# mrShark_15.net
KiCad netlist of a schematic drawn in EAGLE
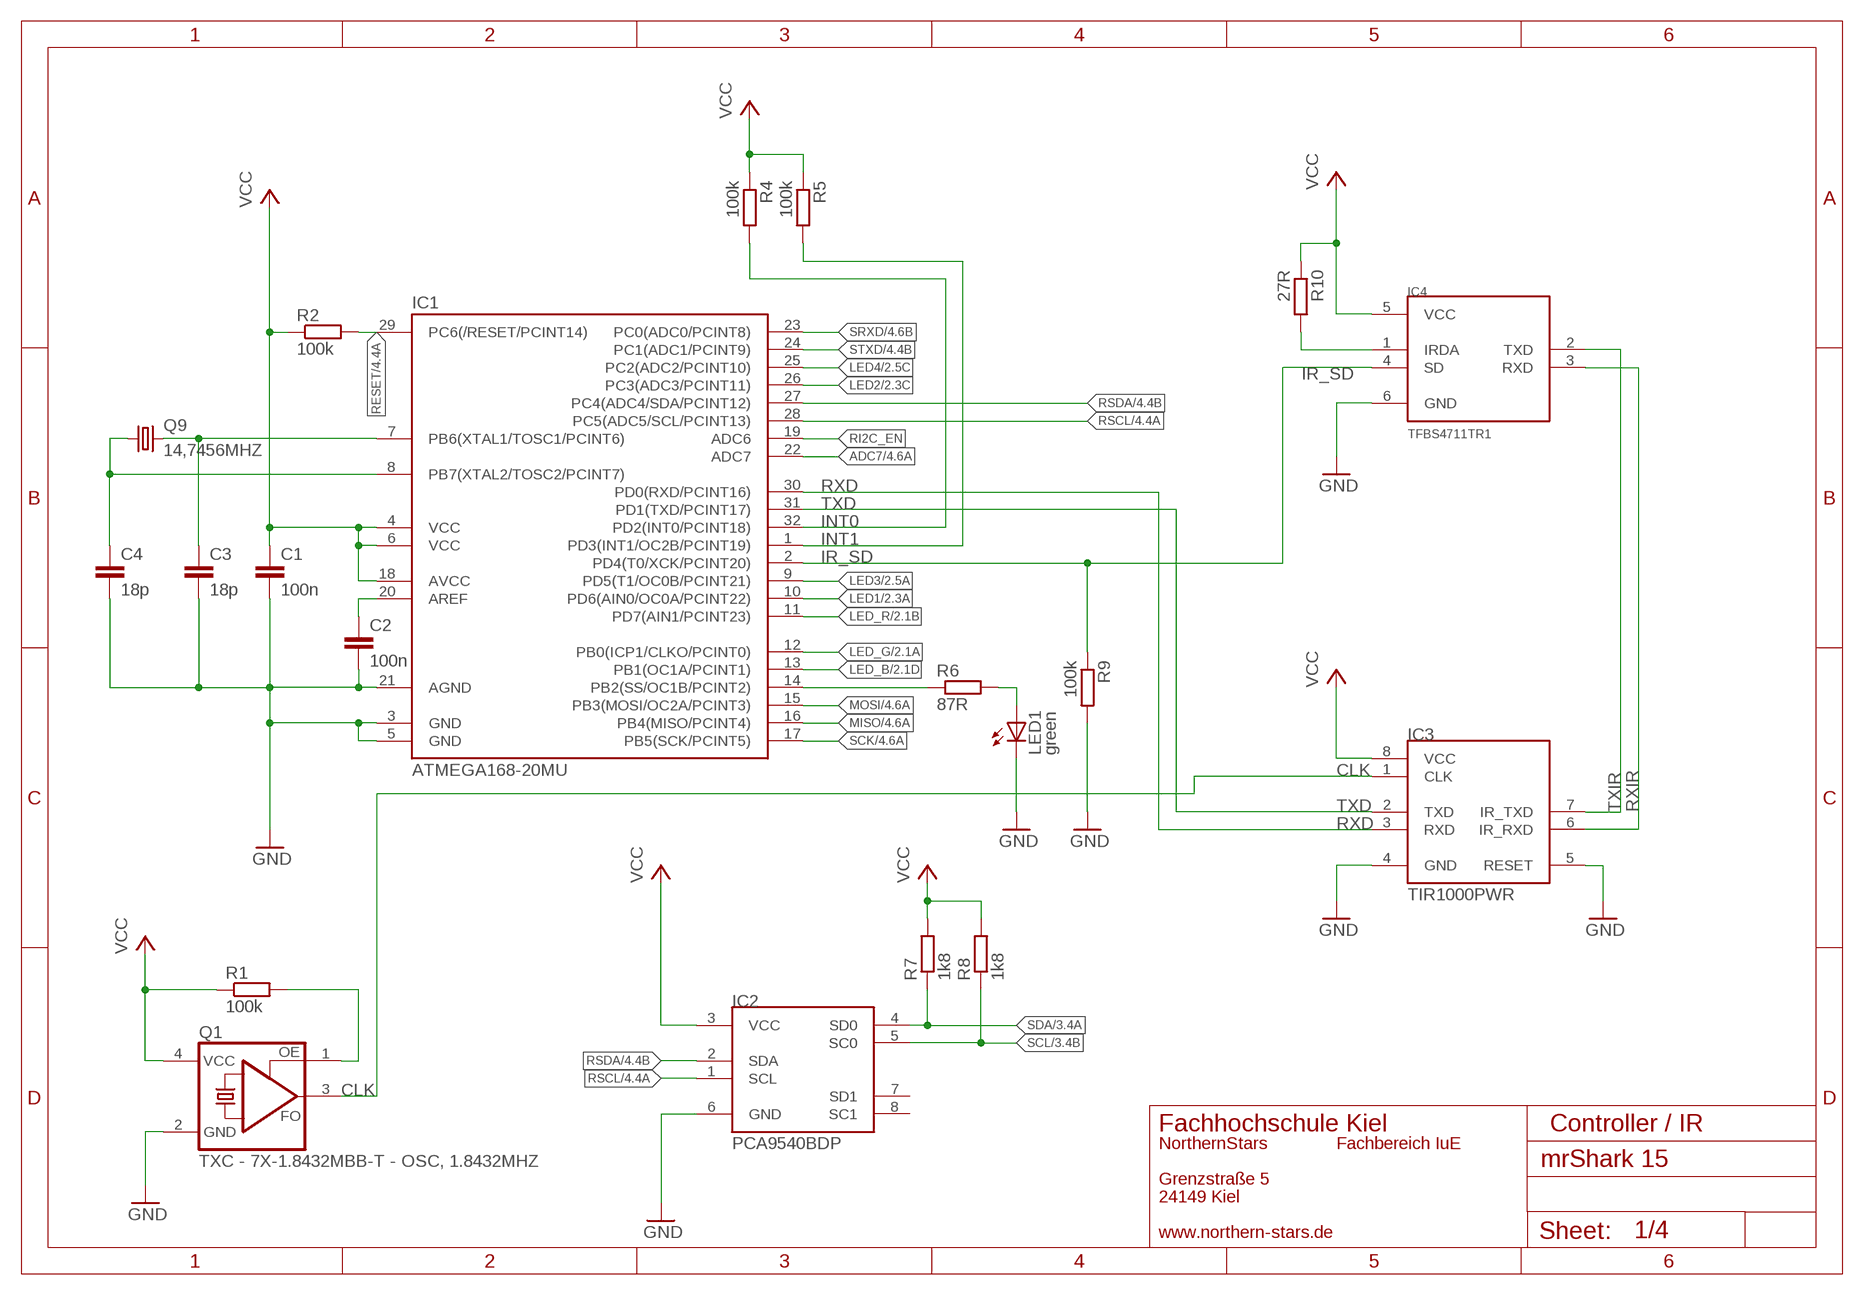
[diagram p0: schematic, sheet 1]
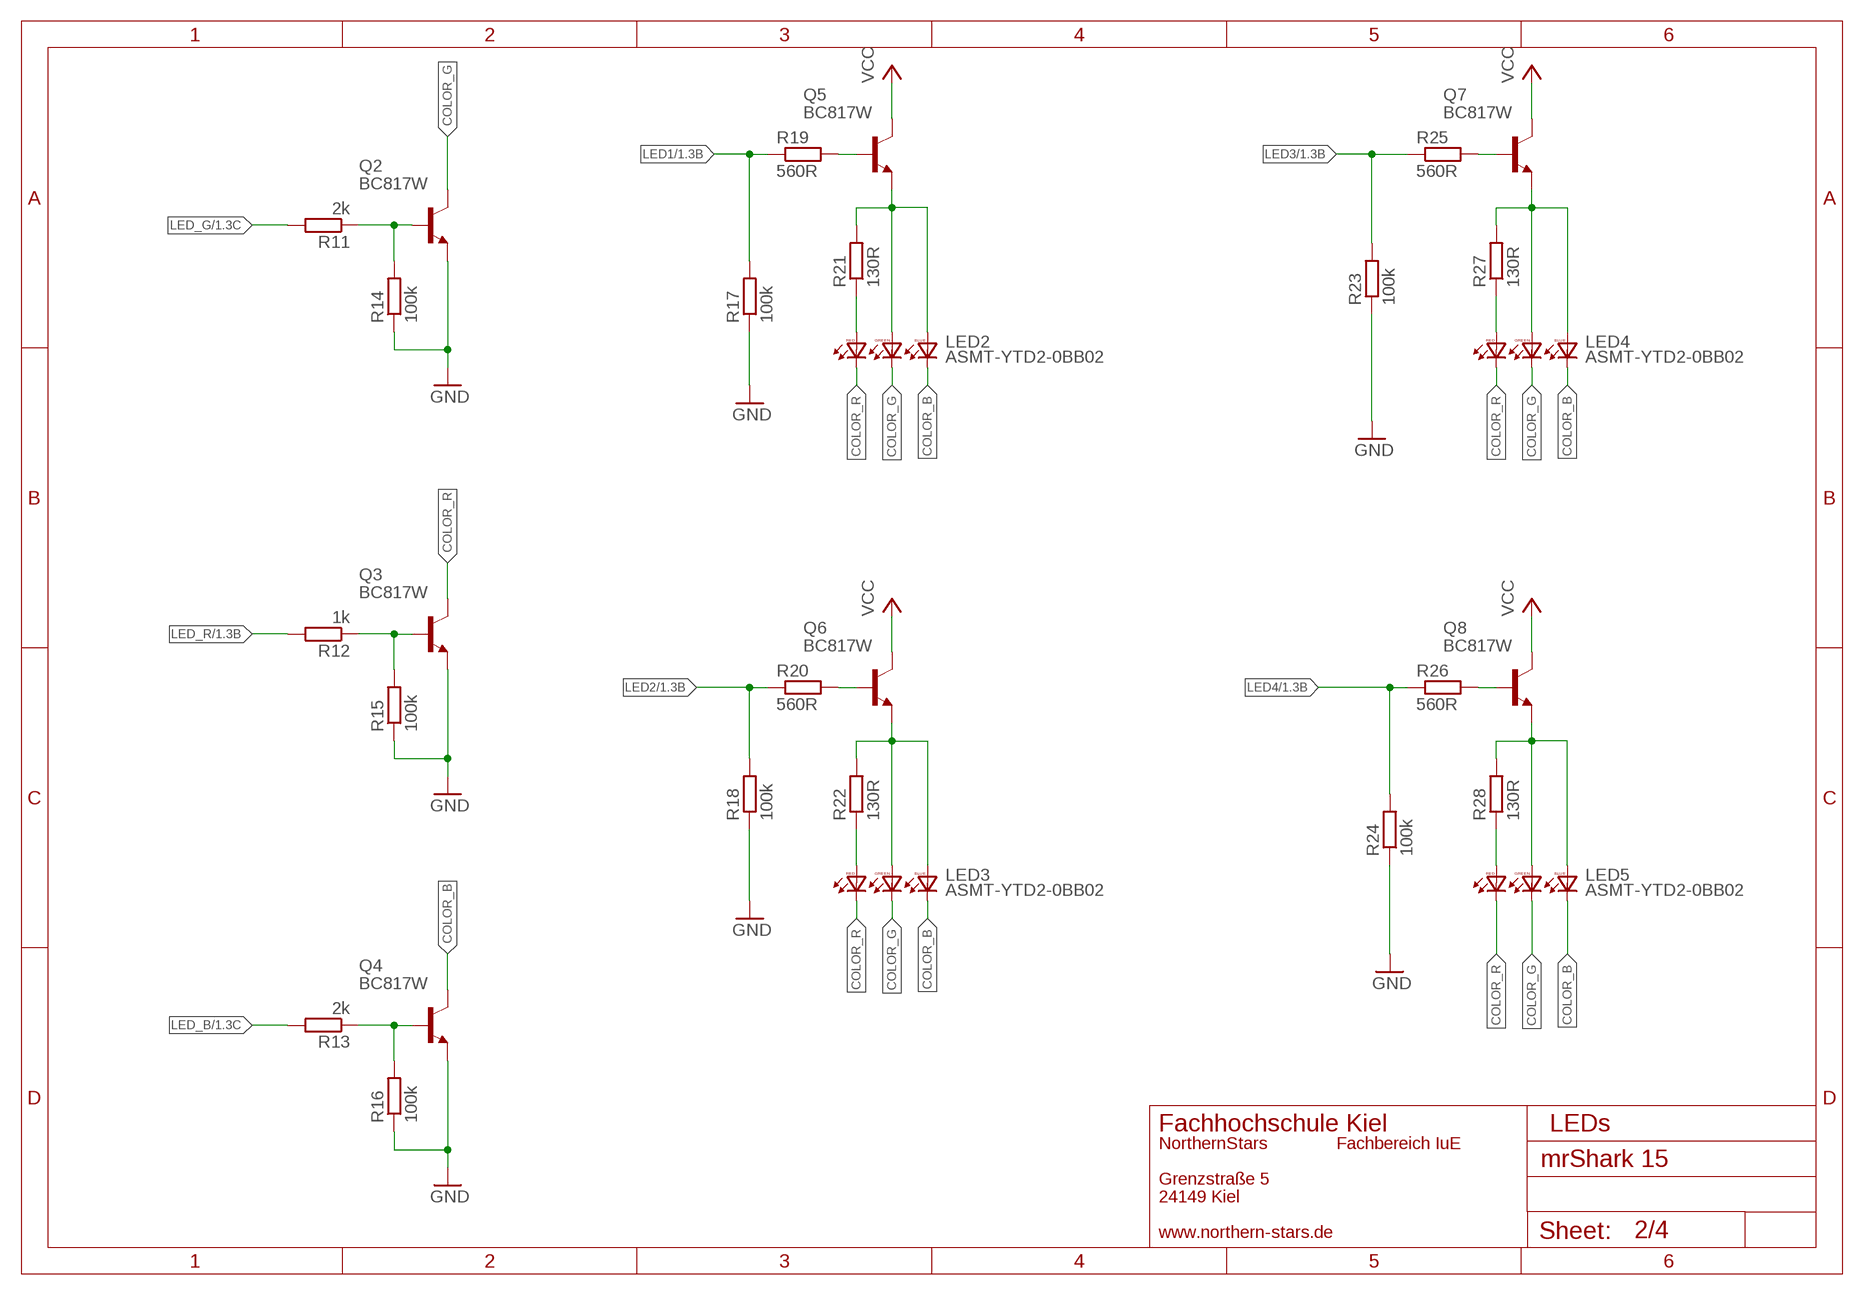
[diagram p1: schematic, sheet 2]
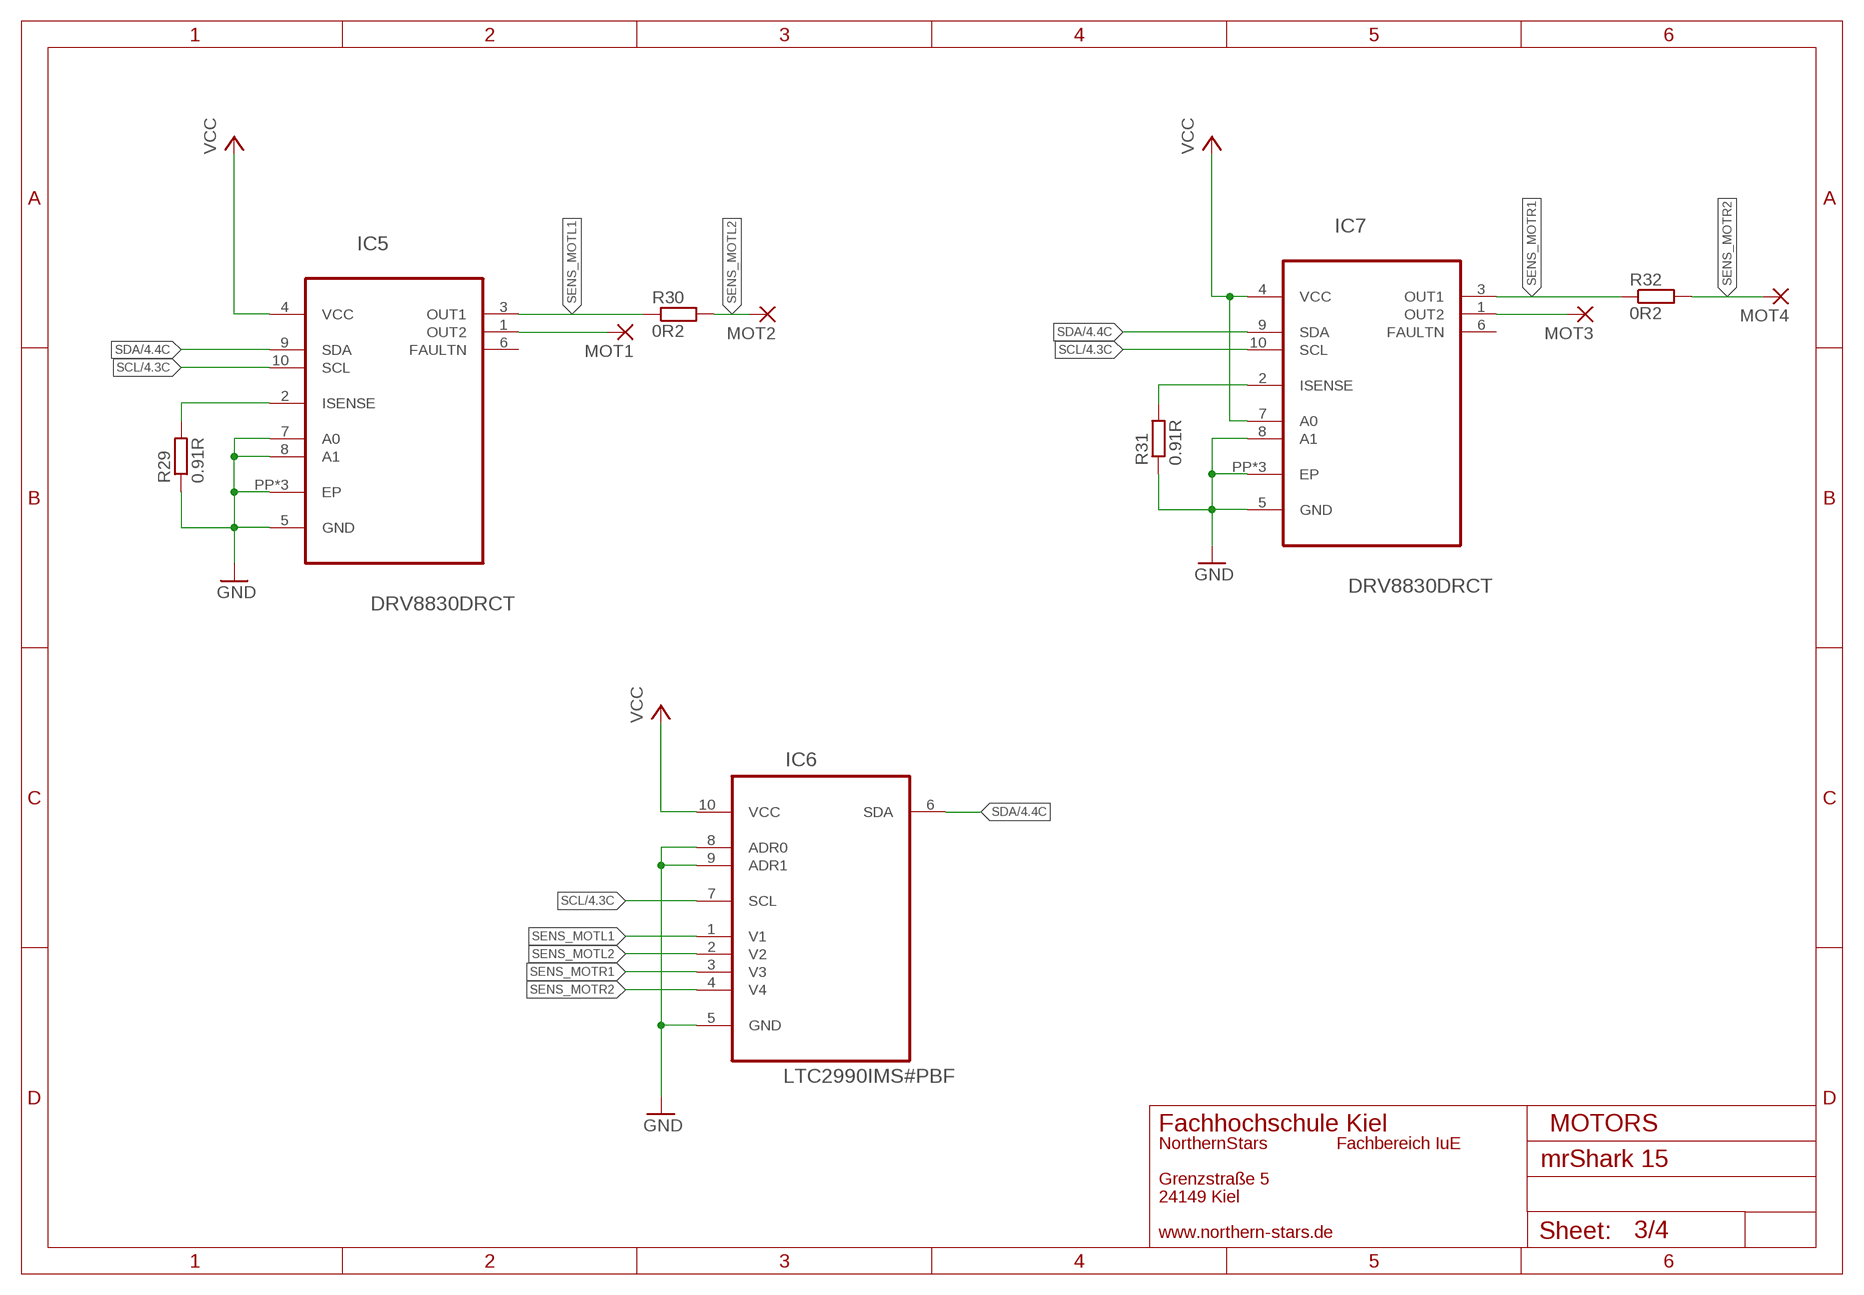
[diagram p2: schematic, sheet 3]
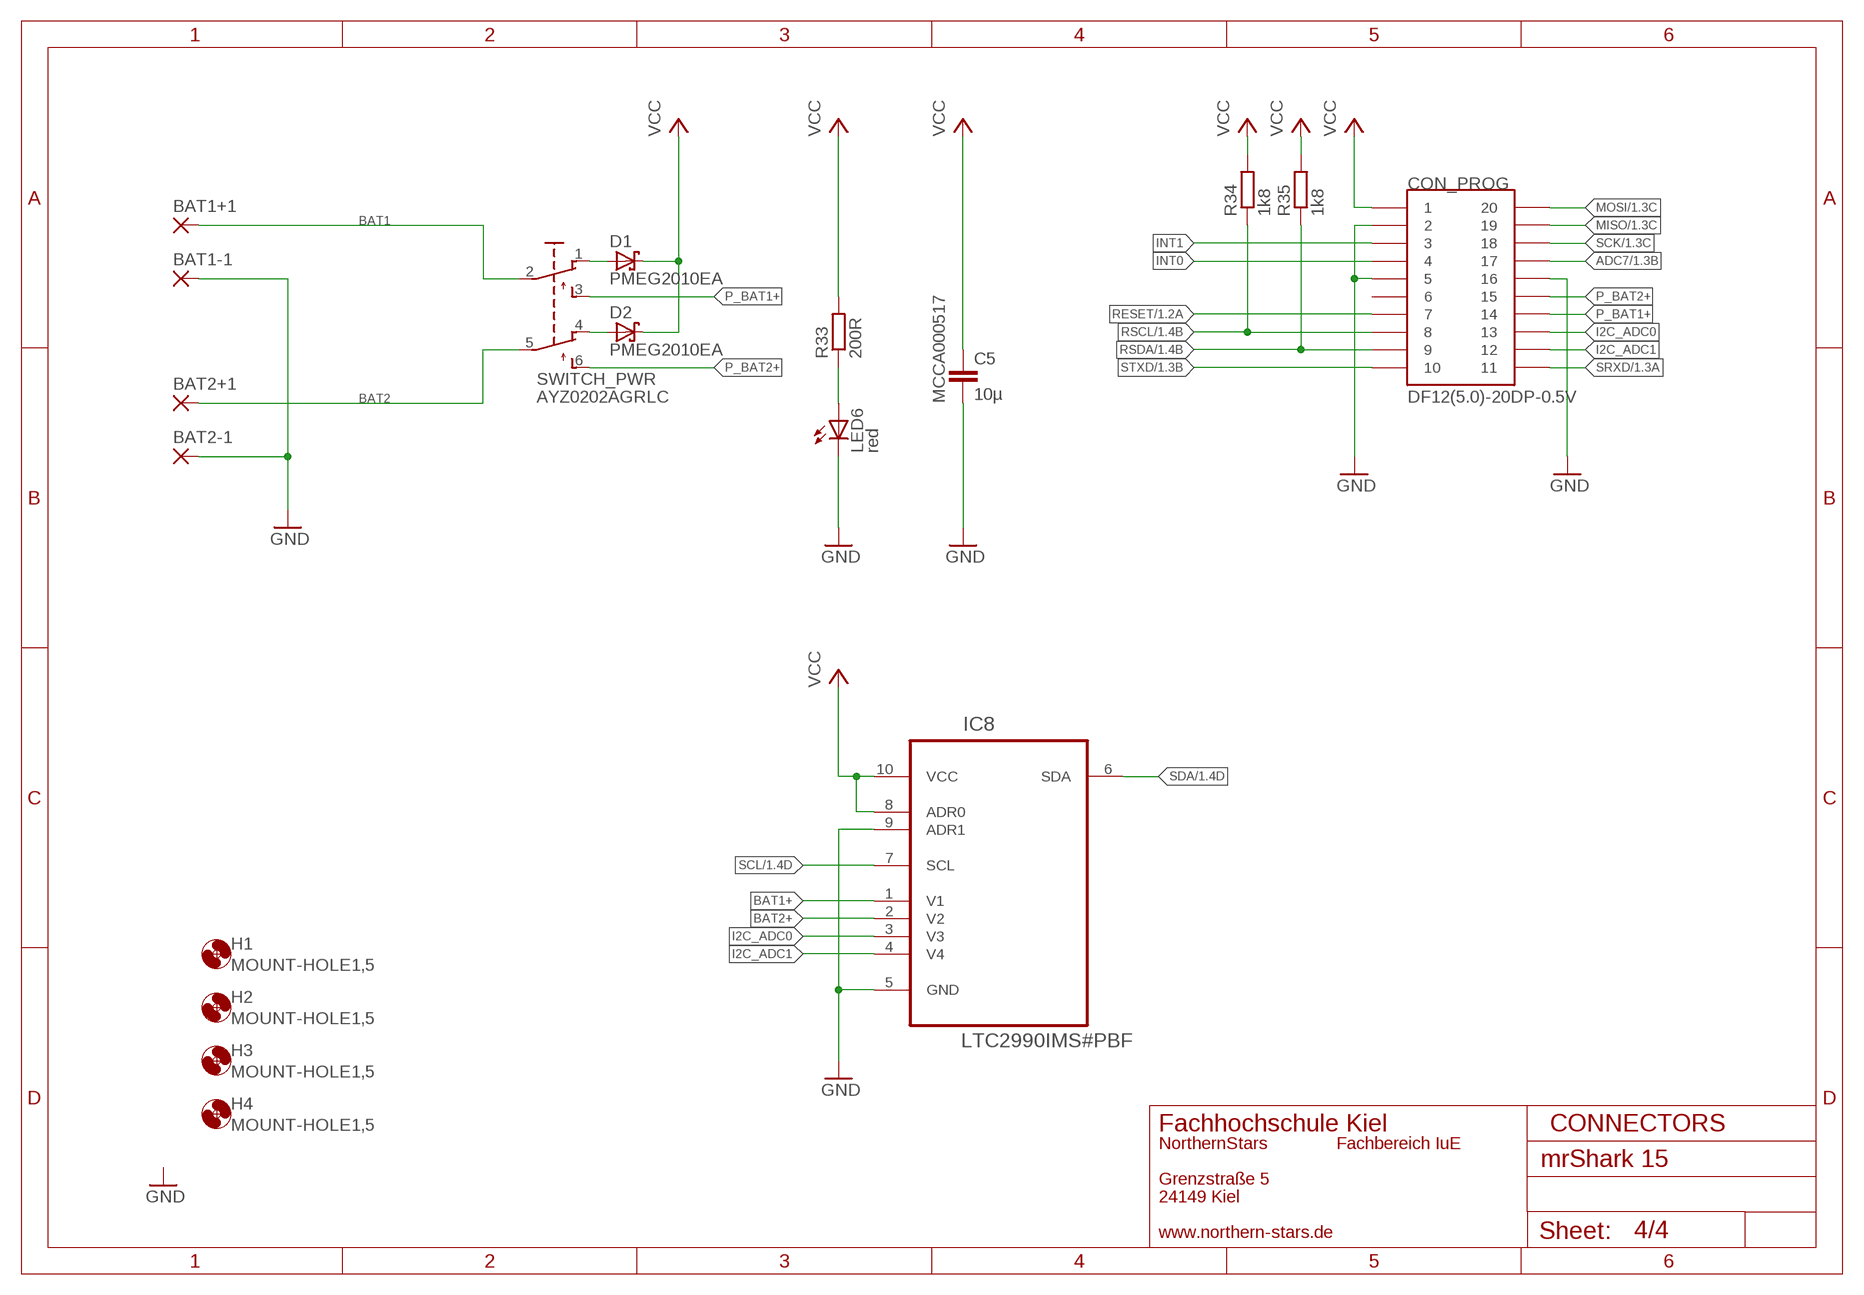
[diagram p3: schematic, sheet 4]

(export (version "E")
  (design (tool "Eeschema 10.0.6"))
  (components
    (comp (ref "IC5")
      (value "DRV8830DRCT")
      (footprint "eagle-import:S-PDSO-N10")
      (libsource (lib "eagle-import") (part "DRV8830DGQRWSON"))
    )
    (comp (ref "IC6")
      (value "LTC2990IMS#PBF")
      (footprint "eagle-import:SOP50P490X110-10N")
      (libsource (lib "eagle-import") (part "LTC2990IMSPBF"))
    )
    (comp (ref "IC7")
      (value "DRV8830DRCT")
      (footprint "eagle-import:S-PDSO-N10")
      (libsource (lib "eagle-import") (part "DRV8830DGQRWSON"))
    )
    (comp (ref "MOT1")
      (value "1,6/0,9")
      (footprint "eagle-import:1,6_0,9")
      (libsource (lib "eagle-import") (part "1,6/0,9"))
    )
    (comp (ref "MOT2")
      (value "1,6/0,9")
      (footprint "eagle-import:1,6_0,9")
      (libsource (lib "eagle-import") (part "1,6/0,9"))
    )
    (comp (ref "MOT3")
      (value "1,6/0,9")
      (footprint "eagle-import:1,6_0,9")
      (libsource (lib "eagle-import") (part "1,6/0,9"))
    )
    (comp (ref "MOT4")
      (value "1,6/0,9")
      (footprint "eagle-import:1,6_0,9")
      (libsource (lib "eagle-import") (part "1,6/0,9"))
    )
    (comp (ref "R29")
      (value "0.91R")
      (footprint "eagle-import:R0603")
      (libsource (lib "eagle-import") (part "R-EU_R0603"))
    )
    (comp (ref "R30")
      (value "0R2")
      (footprint "eagle-import:R0603")
      (libsource (lib "eagle-import") (part "R-EU_R0603"))
    )
    (comp (ref "R31")
      (value "0.91R")
      (footprint "eagle-import:R0603")
      (libsource (lib "eagle-import") (part "R-EU_R0603"))
    )
    (comp (ref "R32")
      (value "0R2")
      (footprint "eagle-import:R0603")
      (libsource (lib "eagle-import") (part "R-EU_R0603"))
    )
    (comp (ref "LED2")
      (value "ASMT-YTD2-0BB02")
      (footprint "eagle-import:PLCC6K")
      (libsource (lib "eagle-import") (part "PLCC6K"))
    )
    (comp (ref "LED3")
      (value "ASMT-YTD2-0BB02")
      (footprint "eagle-import:PLCC6K")
      (libsource (lib "eagle-import") (part "PLCC6K"))
    )
    (comp (ref "LED4")
      (value "ASMT-YTD2-0BB02")
      (footprint "eagle-import:PLCC6K")
      (libsource (lib "eagle-import") (part "PLCC6K"))
    )
    (comp (ref "LED5")
      (value "ASMT-YTD2-0BB02")
      (footprint "eagle-import:PLCC6K")
      (libsource (lib "eagle-import") (part "PLCC6K"))
    )
    (comp (ref "Q2")
      (value "BC817W")
      (footprint "eagle-import:SOT323-BEC")
      (libsource (lib "eagle-import") (part "BC817W"))
    )
    (comp (ref "Q3")
      (value "BC817W")
      (footprint "eagle-import:SOT323-BEC")
      (libsource (lib "eagle-import") (part "BC817W"))
    )
    (comp (ref "Q4")
      (value "BC817W")
      (footprint "eagle-import:SOT323-BEC")
      (libsource (lib "eagle-import") (part "BC817W"))
    )
    (comp (ref "Q5")
      (value "BC817W")
      (footprint "eagle-import:SOT323-BEC")
      (libsource (lib "eagle-import") (part "BC817W"))
    )
    (comp (ref "Q6")
      (value "BC817W")
      (footprint "eagle-import:SOT323-BEC")
      (libsource (lib "eagle-import") (part "BC817W"))
    )
    (comp (ref "Q7")
      (value "BC817W")
      (footprint "eagle-import:SOT323-BEC")
      (libsource (lib "eagle-import") (part "BC817W"))
    )
    (comp (ref "Q8")
      (value "BC817W")
      (footprint "eagle-import:SOT323-BEC")
      (libsource (lib "eagle-import") (part "BC817W"))
    )
    (comp (ref "R11")
      (value "2k")
      (footprint "eagle-import:R0201")
      (libsource (lib "eagle-import") (part "R-EU_R0201"))
    )
    (comp (ref "R12")
      (value "1k")
      (footprint "eagle-import:R0201")
      (libsource (lib "eagle-import") (part "R-EU_R0201"))
    )
    (comp (ref "R13")
      (value "2k")
      (footprint "eagle-import:R0201")
      (libsource (lib "eagle-import") (part "R-EU_R0201"))
    )
    (comp (ref "R14")
      (value "100k")
      (footprint "eagle-import:R0201")
      (libsource (lib "eagle-import") (part "R-EU_R0201"))
    )
    (comp (ref "R15")
      (value "100k")
      (footprint "eagle-import:R0201")
      (libsource (lib "eagle-import") (part "R-EU_R0201"))
    )
    (comp (ref "R16")
      (value "100k")
      (footprint "eagle-import:R0201")
      (libsource (lib "eagle-import") (part "R-EU_R0201"))
    )
    (comp (ref "R17")
      (value "100k")
      (footprint "eagle-import:R0201")
      (libsource (lib "eagle-import") (part "R-EU_R0201"))
    )
    (comp (ref "R18")
      (value "100k")
      (footprint "eagle-import:R0201")
      (libsource (lib "eagle-import") (part "R-EU_R0201"))
    )
    (comp (ref "R19")
      (value "560R")
      (footprint "eagle-import:R0201")
      (libsource (lib "eagle-import") (part "R-EU_R0201"))
    )
    (comp (ref "R20")
      (value "560R")
      (footprint "eagle-import:R0201")
      (libsource (lib "eagle-import") (part "R-EU_R0201"))
    )
    (comp (ref "R21")
      (value "130R")
      (footprint "eagle-import:R0201")
      (libsource (lib "eagle-import") (part "R-EU_R0201"))
    )
    (comp (ref "R22")
      (value "130R")
      (footprint "eagle-import:R0201")
      (libsource (lib "eagle-import") (part "R-EU_R0201"))
    )
    (comp (ref "R23")
      (value "100k")
      (footprint "eagle-import:R0201")
      (libsource (lib "eagle-import") (part "R-EU_R0201"))
    )
    (comp (ref "R24")
      (value "100k")
      (footprint "eagle-import:R0201")
      (libsource (lib "eagle-import") (part "R-EU_R0201"))
    )
    (comp (ref "R25")
      (value "560R")
      (footprint "eagle-import:R0201")
      (libsource (lib "eagle-import") (part "R-EU_R0201"))
    )
    (comp (ref "R26")
      (value "560R")
      (footprint "eagle-import:R0201")
      (libsource (lib "eagle-import") (part "R-EU_R0201"))
    )
    (comp (ref "R27")
      (value "130R")
      (footprint "eagle-import:R0201")
      (libsource (lib "eagle-import") (part "R-EU_R0201"))
    )
    (comp (ref "R28")
      (value "130R")
      (footprint "eagle-import:R0201")
      (libsource (lib "eagle-import") (part "R-EU_R0201"))
    )
    (comp (ref "BAT1+1")
      (value "1,6/0,9")
      (footprint "eagle-import:1,6_0,9")
      (libsource (lib "eagle-import") (part "1,6/0,9"))
    )
    (comp (ref "BAT1-1")
      (value "1,6/0,9")
      (footprint "eagle-import:1,6_0,9")
      (libsource (lib "eagle-import") (part "1,6/0,9"))
    )
    (comp (ref "BAT2+1")
      (value "1,6/0,9")
      (footprint "eagle-import:1,6_0,9")
      (libsource (lib "eagle-import") (part "1,6/0,9"))
    )
    (comp (ref "BAT2-1")
      (value "1,6/0,9")
      (footprint "eagle-import:1,6_0,9")
      (libsource (lib "eagle-import") (part "1,6/0,9"))
    )
    (comp (ref "C5")
      (value "10µ")
      (footprint "eagle-import:C0603K")
      (libsource (lib "eagle-import") (part "C-EUC0603K"))
    )
    (comp (ref "CON_PROG")
      (value "DF12(5.0)-20DP-0.5V")
      (footprint "eagle-import:DF12-20DP")
      (libsource (lib "eagle-import") (part "DF12-20DP"))
    )
    (comp (ref "D1")
      (value "PMEG2010EA")
      (footprint "eagle-import:SOD323-R")
      (libsource (lib "eagle-import") (part "PMEG2010EAR"))
    )
    (comp (ref "D2")
      (value "PMEG2010EA")
      (footprint "eagle-import:SOD323-R")
      (libsource (lib "eagle-import") (part "PMEG2010EAR"))
    )
    (comp (ref "H1")
      (value "MOUNT-HOLE1,5")
      (footprint "eagle-import:1,5")
      (libsource (lib "eagle-import") (part "MOUNT-HOLE1,5"))
    )
    (comp (ref "H2")
      (value "MOUNT-HOLE1,5")
      (footprint "eagle-import:1,5")
      (libsource (lib "eagle-import") (part "MOUNT-HOLE1,5"))
    )
    (comp (ref "H3")
      (value "MOUNT-HOLE1,5")
      (footprint "eagle-import:1,5")
      (libsource (lib "eagle-import") (part "MOUNT-HOLE1,5"))
    )
    (comp (ref "H4")
      (value "MOUNT-HOLE1,5")
      (footprint "eagle-import:1,5")
      (libsource (lib "eagle-import") (part "MOUNT-HOLE1,5"))
    )
    (comp (ref "IC8")
      (value "LTC2990IMS#PBF")
      (footprint "eagle-import:SOP50P490X110-10N")
      (libsource (lib "eagle-import") (part "LTC2990IMSPBF"))
    )
    (comp (ref "LED6")
      (value "red")
      (footprint "eagle-import:CHIPLED_0603")
      (libsource (lib "eagle-import") (part "LEDCHIPLED_0603"))
    )
    (comp (ref "R33")
      (value "200R")
      (footprint "eagle-import:R0201")
      (libsource (lib "eagle-import") (part "R-EU_R0201"))
    )
    (comp (ref "R34")
      (value "1k8")
      (footprint "eagle-import:R0201")
      (libsource (lib "eagle-import") (part "R-EU_R0201"))
    )
    (comp (ref "R35")
      (value "1k8")
      (footprint "eagle-import:R0201")
      (libsource (lib "eagle-import") (part "R-EU_R0201"))
    )
    (comp (ref "SWITCH_PWR")
      (value "AYZ0202AGRLC")
      (footprint "eagle-import:AYZ0202AGLRC")
      (libsource (lib "eagle-import") (part "AYZ0202AGRLC"))
    )
    (comp (ref "C1")
      (value "100n")
      (footprint "eagle-import:C0201")
      (libsource (lib "eagle-import") (part "C-EUC0201"))
    )
    (comp (ref "C2")
      (value "100n")
      (footprint "eagle-import:C0201")
      (libsource (lib "eagle-import") (part "C-EUC0201"))
    )
    (comp (ref "C3")
      (value "18p")
      (footprint "eagle-import:C0201")
      (libsource (lib "eagle-import") (part "C-EUC0201"))
    )
    (comp (ref "C4")
      (value "18p")
      (footprint "eagle-import:C0201")
      (libsource (lib "eagle-import") (part "C-EUC0201"))
    )
    (comp (ref "IC1")
      (value "ATMEGA168-20MU")
      (footprint "eagle-import:MLF32")
      (libsource (lib "eagle-import") (part "ATMEGA48/88/168-MU"))
    )
    (comp (ref "IC2")
      (value "PCA9540BDP")
      (footprint "eagle-import:TSSOP8")
      (libsource (lib "eagle-import") (part "PCA9540TSSOP8"))
    )
    (comp (ref "IC3")
      (value "TIR1000PWR")
      (footprint "eagle-import:PW_R-PDSO-G08")
      (libsource (lib "eagle-import") (part "TIR1000PWR"))
    )
    (comp (ref "IC4")
      (value "TFBS4711TR1")
      (footprint "eagle-import:TFBS4711")
      (libsource (lib "eagle-import") (part "TFBS4711TR1"))
    )
    (comp (ref "LED1")
      (value "green")
      (footprint "eagle-import:CHIPLED_0603")
      (libsource (lib "eagle-import") (part "LEDCHIPLED_0603"))
    )
    (comp (ref "Q1")
      (value "TXC - 7X-1.8432MBB-T - OSC, 1.8432MHZ")
      (footprint "eagle-import:3.2X2.5")
      (libsource (lib "eagle-import") (part "7X-SERIES"))
    )
    (comp (ref "Q9")
      (value "14,7456MHZ")
      (footprint "eagle-import:TXC_7B_SERIES")
      (libsource (lib "eagle-import") (part "TXC-7B-SERIESSMD"))
    )
    (comp (ref "R1")
      (value "100k")
      (footprint "eagle-import:R0201")
      (libsource (lib "eagle-import") (part "R-EU_R0201"))
    )
    (comp (ref "R2")
      (value "100k")
      (footprint "eagle-import:R0201")
      (libsource (lib "eagle-import") (part "R-EU_R0201"))
    )
    (comp (ref "R4")
      (value "100k")
      (footprint "eagle-import:R0201")
      (libsource (lib "eagle-import") (part "R-EU_R0201"))
    )
    (comp (ref "R5")
      (value "100k")
      (footprint "eagle-import:R0201")
      (libsource (lib "eagle-import") (part "R-EU_R0201"))
    )
    (comp (ref "R6")
      (value "87R")
      (footprint "eagle-import:R0201")
      (libsource (lib "eagle-import") (part "R-EU_R0201"))
    )
    (comp (ref "R7")
      (value "1k8")
      (footprint "eagle-import:R0201")
      (libsource (lib "eagle-import") (part "R-EU_R0201"))
    )
    (comp (ref "R8")
      (value "1k8")
      (footprint "eagle-import:R0201")
      (libsource (lib "eagle-import") (part "R-EU_R0201"))
    )
    (comp (ref "R9")
      (value "100k")
      (footprint "eagle-import:R0201")
      (libsource (lib "eagle-import") (part "R-EU_R0201"))
    )
    (comp (ref "R10")
      (value "27R")
      (footprint "eagle-import:R0201")
      (libsource (lib "eagle-import") (part "R-EU_R0201"))
    )
  )
  (nets
    (net (code "1") (name "ADC7") (class "Default")
      (node (ref "CON_PROG") (pin "17") (pinfunction "17_17") (pintype "bidirectional"))
      (node (ref "IC1") (pin "22") (pinfunction "ADC7_22") (pintype "passive"))
    )
    (net (code "2") (name "BAT1") (class "Default")
      (node (ref "BAT1+1") (pin "1") (pinfunction "P_1") (pintype "passive"))
      (node (ref "SWITCH_PWR") (pin "2") (pinfunction "P_2") (pintype "passive"))
    )
    (net (code "3") (name "BAT1+") (class "Default")
      (node (ref "D1") (pin "A") (pinfunction "A_A") (pintype "passive"))
      (node (ref "IC8") (pin "1") (pinfunction "V1_1") (pintype "input"))
      (node (ref "SWITCH_PWR") (pin "1") (pinfunction "O_1") (pintype "passive"))
    )
    (net (code "4") (name "BAT2") (class "Default")
      (node (ref "BAT2+1") (pin "1") (pinfunction "P_1") (pintype "passive"))
      (node (ref "SWITCH_PWR") (pin "5") (pinfunction "P1_5") (pintype "passive"))
    )
    (net (code "5") (name "BAT2+") (class "Default")
      (node (ref "D2") (pin "A") (pinfunction "A_A") (pintype "passive"))
      (node (ref "IC8") (pin "2") (pinfunction "V2_2") (pintype "input"))
      (node (ref "SWITCH_PWR") (pin "4") (pinfunction "O1_4") (pintype "passive"))
    )
    (net (code "6") (name "CLK") (class "Default")
      (node (ref "IC3") (pin "1") (pinfunction "CLK_1") (pintype "bidirectional"))
      (node (ref "Q1") (pin "3") (pinfunction "FO_3") (pintype "output"))
    )
    (net (code "7") (name "COLOR_B") (class "Default")
      (node (ref "LED2") (pin "1") (pinfunction "BC_1") (pintype "passive"))
      (node (ref "LED3") (pin "1") (pinfunction "BC_1") (pintype "passive"))
      (node (ref "LED4") (pin "1") (pinfunction "BC_1") (pintype "passive"))
      (node (ref "LED5") (pin "1") (pinfunction "BC_1") (pintype "passive"))
      (node (ref "Q4") (pin "C") (pinfunction "C_C") (pintype "passive"))
    )
    (net (code "8") (name "COLOR_G") (class "Default")
      (node (ref "LED2") (pin "2") (pinfunction "GC_2") (pintype "passive"))
      (node (ref "LED3") (pin "2") (pinfunction "GC_2") (pintype "passive"))
      (node (ref "LED4") (pin "2") (pinfunction "GC_2") (pintype "passive"))
      (node (ref "LED5") (pin "2") (pinfunction "GC_2") (pintype "passive"))
      (node (ref "Q2") (pin "C") (pinfunction "C_C") (pintype "passive"))
    )
    (net (code "9") (name "COLOR_R") (class "Default")
      (node (ref "LED2") (pin "3") (pinfunction "RC_3") (pintype "passive"))
      (node (ref "LED3") (pin "3") (pinfunction "RC_3") (pintype "passive"))
      (node (ref "LED4") (pin "3") (pinfunction "RC_3") (pintype "passive"))
      (node (ref "LED5") (pin "3") (pinfunction "RC_3") (pintype "passive"))
      (node (ref "Q3") (pin "C") (pinfunction "C_C") (pintype "passive"))
    )
    (net (code "10") (name "GND") (class "Default")
      (node (ref "BAT1-1") (pin "1") (pinfunction "P_1") (pintype "passive"))
      (node (ref "BAT2-1") (pin "1") (pinfunction "P_1") (pintype "passive"))
      (node (ref "C1") (pin "2") (pinfunction "2_2") (pintype "passive"))
      (node (ref "C2") (pin "2") (pinfunction "2_2") (pintype "passive"))
      (node (ref "C3") (pin "2") (pinfunction "2_2") (pintype "passive"))
      (node (ref "C4") (pin "2") (pinfunction "2_2") (pintype "passive"))
      (node (ref "C5") (pin "2") (pinfunction "2_2") (pintype "passive"))
      (node (ref "CON_PROG") (pin "16") (pinfunction "16_16") (pintype "bidirectional"))
      (node (ref "CON_PROG") (pin "2") (pinfunction "2_2") (pintype "bidirectional"))
      (node (ref "CON_PROG") (pin "5") (pinfunction "5_5") (pintype "bidirectional"))
      (node (ref "IC1") (pin "21") (pinfunction "AGND_21") (pintype "power_in"))
      (node (ref "IC1") (pin "3") (pinfunction "GND_3") (pintype "power_in"))
      (node (ref "IC1") (pin "5") (pinfunction "GND_5") (pintype "power_in"))
      (node (ref "IC2") (pin "6") (pinfunction "GND_6") (pintype "bidirectional"))
      (node (ref "IC3") (pin "4") (pinfunction "GND_4") (pintype "bidirectional"))
      (node (ref "IC3") (pin "5") (pinfunction "RESET_5") (pintype "bidirectional"))
      (node (ref "IC4") (pin "6") (pinfunction "GND_6") (pintype "bidirectional"))
      (node (ref "IC5") (pin "5") (pinfunction "GND_5") (pintype "passive"))
      (node (ref "IC5") (pin "7") (pinfunction "A0_7") (pintype "input"))
      (node (ref "IC5") (pin "8") (pinfunction "A1_8") (pintype "input"))
      (node (ref "IC5") (pin "PP") (pinfunction "EP_PP") (pintype "passive"))
      (node (ref "IC5") (pin "PP@1") (pinfunction "EP_PP@1") (pintype "passive"))
      (node (ref "IC5") (pin "PP@2") (pinfunction "EP_PP@2") (pintype "passive"))
      (node (ref "IC6") (pin "5") (pinfunction "GND_5") (pintype "passive"))
      (node (ref "IC6") (pin "8") (pinfunction "ADR0_8") (pintype "input"))
      (node (ref "IC6") (pin "9") (pinfunction "ADR1_9") (pintype "input"))
      (node (ref "IC7") (pin "5") (pinfunction "GND_5") (pintype "passive"))
      (node (ref "IC7") (pin "8") (pinfunction "A1_8") (pintype "input"))
      (node (ref "IC7") (pin "PP") (pinfunction "EP_PP") (pintype "passive"))
      (node (ref "IC7") (pin "PP@1") (pinfunction "EP_PP@1") (pintype "passive"))
      (node (ref "IC7") (pin "PP@2") (pinfunction "EP_PP@2") (pintype "passive"))
      (node (ref "IC8") (pin "5") (pinfunction "GND_5") (pintype "passive"))
      (node (ref "IC8") (pin "9") (pinfunction "ADR1_9") (pintype "input"))
      (node (ref "LED1") (pin "C") (pinfunction "C_C") (pintype "passive"))
      (node (ref "LED6") (pin "C") (pinfunction "C_C") (pintype "passive"))
      (node (ref "Q1") (pin "2") (pinfunction "GND_2") (pintype "power_in"))
      (node (ref "Q2") (pin "E") (pinfunction "E_E") (pintype "passive"))
      (node (ref "Q3") (pin "E") (pinfunction "E_E") (pintype "passive"))
      (node (ref "Q4") (pin "E") (pinfunction "E_E") (pintype "passive"))
      (node (ref "R14") (pin "1") (pinfunction "1_1") (pintype "passive"))
      (node (ref "R15") (pin "1") (pinfunction "1_1") (pintype "passive"))
      (node (ref "R16") (pin "1") (pinfunction "1_1") (pintype "passive"))
      (node (ref "R17") (pin "1") (pinfunction "1_1") (pintype "passive"))
      (node (ref "R18") (pin "1") (pinfunction "1_1") (pintype "passive"))
      (node (ref "R23") (pin "1") (pinfunction "1_1") (pintype "passive"))
      (node (ref "R24") (pin "1") (pinfunction "1_1") (pintype "passive"))
      (node (ref "R29") (pin "1") (pinfunction "1_1") (pintype "passive"))
      (node (ref "R31") (pin "1") (pinfunction "1_1") (pintype "passive"))
      (node (ref "R9") (pin "2") (pinfunction "2_2") (pintype "passive"))
    )
    (net (code "11") (name "I2C_ADC0") (class "Default")
      (node (ref "CON_PROG") (pin "13") (pinfunction "13_13") (pintype "bidirectional"))
      (node (ref "IC8") (pin "3") (pinfunction "V3_3") (pintype "input"))
    )
    (net (code "12") (name "I2C_ADC1") (class "Default")
      (node (ref "CON_PROG") (pin "12") (pinfunction "12_12") (pintype "bidirectional"))
      (node (ref "IC8") (pin "4") (pinfunction "V4_4") (pintype "input"))
    )
    (net (code "13") (name "INT0") (class "Default")
      (node (ref "CON_PROG") (pin "4") (pinfunction "4_4") (pintype "bidirectional"))
      (node (ref "IC1") (pin "32") (pinfunction "PD2(INT0/PCINT18)_32") (pintype "bidirectional"))
      (node (ref "R4") (pin "2") (pinfunction "2_2") (pintype "passive"))
    )
    (net (code "14") (name "INT1") (class "Default")
      (node (ref "CON_PROG") (pin "3") (pinfunction "3_3") (pintype "bidirectional"))
      (node (ref "IC1") (pin "1") (pinfunction "PD3(INT1/OC2B/PCINT19)_1") (pintype "bidirectional"))
      (node (ref "R5") (pin "2") (pinfunction "2_2") (pintype "passive"))
    )
    (net (code "15") (name "IR_SD") (class "Default")
      (node (ref "IC1") (pin "2") (pinfunction "PD4(T0/XCK/PCINT20)_2") (pintype "bidirectional"))
      (node (ref "IC4") (pin "4") (pinfunction "SD_4") (pintype "bidirectional"))
      (node (ref "R9") (pin "1") (pinfunction "1_1") (pintype "passive"))
    )
    (net (code "16") (name "LED1") (class "Default")
      (node (ref "IC1") (pin "10") (pinfunction "PD6(AIN0/OC0A/PCINT22)_10") (pintype "bidirectional"))
      (node (ref "R17") (pin "2") (pinfunction "2_2") (pintype "passive"))
      (node (ref "R19") (pin "1") (pinfunction "1_1") (pintype "passive"))
    )
    (net (code "17") (name "LED2") (class "Default")
      (node (ref "IC1") (pin "26") (pinfunction "PC3(ADC3/PCINT11)_26") (pintype "bidirectional"))
      (node (ref "R18") (pin "2") (pinfunction "2_2") (pintype "passive"))
      (node (ref "R20") (pin "1") (pinfunction "1_1") (pintype "passive"))
    )
    (net (code "18") (name "LED3") (class "Default")
      (node (ref "IC1") (pin "9") (pinfunction "PD5(T1/OC0B/PCINT21)_9") (pintype "bidirectional"))
      (node (ref "R23") (pin "2") (pinfunction "2_2") (pintype "passive"))
      (node (ref "R25") (pin "1") (pinfunction "1_1") (pintype "passive"))
    )
    (net (code "19") (name "LED4") (class "Default")
      (node (ref "IC1") (pin "25") (pinfunction "PC2(ADC2/PCINT10)_25") (pintype "bidirectional"))
      (node (ref "R24") (pin "2") (pinfunction "2_2") (pintype "passive"))
      (node (ref "R26") (pin "1") (pinfunction "1_1") (pintype "passive"))
    )
    (net (code "20") (name "LED_B") (class "Default")
      (node (ref "IC1") (pin "13") (pinfunction "PB1(OC1A/PCINT1)_13") (pintype "bidirectional"))
      (node (ref "R13") (pin "2") (pinfunction "2_2") (pintype "passive"))
    )
    (net (code "21") (name "LED_G") (class "Default")
      (node (ref "IC1") (pin "12") (pinfunction "PB0(ICP1/CLKO/PCINT0)_12") (pintype "bidirectional"))
      (node (ref "R11") (pin "2") (pinfunction "2_2") (pintype "passive"))
    )
    (net (code "22") (name "LED_R") (class "Default")
      (node (ref "IC1") (pin "11") (pinfunction "PD7(AIN1/PCINT23)_11") (pintype "bidirectional"))
      (node (ref "R12") (pin "2") (pinfunction "2_2") (pintype "passive"))
    )
    (net (code "23") (name "MISO") (class "Default")
      (node (ref "CON_PROG") (pin "19") (pinfunction "19_19") (pintype "bidirectional"))
      (node (ref "IC1") (pin "16") (pinfunction "PB4(MISO/PCINT4)_16") (pintype "bidirectional"))
    )
    (net (code "24") (name "MOSI") (class "Default")
      (node (ref "CON_PROG") (pin "20") (pinfunction "20_20") (pintype "bidirectional"))
      (node (ref "IC1") (pin "15") (pinfunction "PB3(MOSI/OC2A/PCINT3)_15") (pintype "bidirectional"))
    )
    (net (code "25") (name "Net-(IC1-AREF)") (class "Default")
      (node (ref "C2") (pin "1") (pinfunction "1_1") (pintype "passive"))
      (node (ref "IC1") (pin "20") (pinfunction "AREF_20") (pintype "passive"))
    )
    (net (code "26") (name "Net-(IC1-PB2(SS{slash}OC1B{slash}PCINT2))") (class "Default")
      (node (ref "IC1") (pin "14") (pinfunction "PB2(SS/OC1B/PCINT2)_14") (pintype "bidirectional"))
      (node (ref "R6") (pin "1") (pinfunction "1_1") (pintype "passive"))
    )
    (net (code "27") (name "Net-(IC1-PB6(XTAL1{slash}TOSC1{slash}PCINT6))") (class "Default")
      (node (ref "C3") (pin "1") (pinfunction "1_1") (pintype "passive"))
      (node (ref "IC1") (pin "7") (pinfunction "PB6(XTAL1/TOSC1/PCINT6)_7") (pintype "bidirectional"))
      (node (ref "Q9") (pin "3") (pinfunction "2_3") (pintype "passive"))
    )
    (net (code "28") (name "Net-(IC1-PB7(XTAL2{slash}TOSC2{slash}PCINT7))") (class "Default")
      (node (ref "C4") (pin "1") (pinfunction "1_1") (pintype "passive"))
      (node (ref "IC1") (pin "8") (pinfunction "PB7(XTAL2/TOSC2/PCINT7)_8") (pintype "bidirectional"))
      (node (ref "Q9") (pin "1") (pinfunction "1_1") (pintype "passive"))
    )
    (net (code "29") (name "Net-(IC4-IRDA)") (class "Default")
      (node (ref "IC4") (pin "1") (pinfunction "IRDA_1") (pintype "bidirectional"))
      (node (ref "R10") (pin "2") (pinfunction "2_2") (pintype "passive"))
    )
    (net (code "30") (name "Net-(IC5-ISENSE)") (class "Default")
      (node (ref "IC5") (pin "2") (pinfunction "ISENSE_2") (pintype "input"))
      (node (ref "R29") (pin "2") (pinfunction "2_2") (pintype "passive"))
    )
    (net (code "31") (name "Net-(IC5-OUT2)") (class "Default")
      (node (ref "IC5") (pin "1") (pinfunction "OUT2_1") (pintype "output"))
      (node (ref "MOT1") (pin "1") (pinfunction "P_1") (pintype "passive"))
    )
    (net (code "32") (name "Net-(IC7-ISENSE)") (class "Default")
      (node (ref "IC7") (pin "2") (pinfunction "ISENSE_2") (pintype "input"))
      (node (ref "R31") (pin "2") (pinfunction "2_2") (pintype "passive"))
    )
    (net (code "33") (name "Net-(IC7-OUT2)") (class "Default")
      (node (ref "IC7") (pin "1") (pinfunction "OUT2_1") (pintype "output"))
      (node (ref "MOT3") (pin "1") (pinfunction "P_1") (pintype "passive"))
    )
    (net (code "34") (name "Net-(LED1-PadA)") (class "Default")
      (node (ref "LED1") (pin "A") (pinfunction "A_A") (pintype "passive"))
      (node (ref "R6") (pin "2") (pinfunction "2_2") (pintype "passive"))
    )
    (net (code "35") (name "Net-(LED2-BA)") (class "Default")
      (node (ref "LED2") (pin "5") (pinfunction "GA_5") (pintype "passive"))
      (node (ref "LED2") (pin "6") (pinfunction "BA_6") (pintype "passive"))
      (node (ref "Q5") (pin "E") (pinfunction "E_E") (pintype "passive"))
      (node (ref "R21") (pin "2") (pinfunction "2_2") (pintype "passive"))
    )
    (net (code "36") (name "Net-(LED2-RA)") (class "Default")
      (node (ref "LED2") (pin "4") (pinfunction "RA_4") (pintype "passive"))
      (node (ref "R21") (pin "1") (pinfunction "1_1") (pintype "passive"))
    )
    (net (code "37") (name "Net-(LED3-BA)") (class "Default")
      (node (ref "LED3") (pin "5") (pinfunction "GA_5") (pintype "passive"))
      (node (ref "LED3") (pin "6") (pinfunction "BA_6") (pintype "passive"))
      (node (ref "Q6") (pin "E") (pinfunction "E_E") (pintype "passive"))
      (node (ref "R22") (pin "2") (pinfunction "2_2") (pintype "passive"))
    )
    (net (code "38") (name "Net-(LED3-RA)") (class "Default")
      (node (ref "LED3") (pin "4") (pinfunction "RA_4") (pintype "passive"))
      (node (ref "R22") (pin "1") (pinfunction "1_1") (pintype "passive"))
    )
    (net (code "39") (name "Net-(LED4-BA)") (class "Default")
      (node (ref "LED4") (pin "5") (pinfunction "GA_5") (pintype "passive"))
      (node (ref "LED4") (pin "6") (pinfunction "BA_6") (pintype "passive"))
      (node (ref "Q7") (pin "E") (pinfunction "E_E") (pintype "passive"))
      (node (ref "R27") (pin "2") (pinfunction "2_2") (pintype "passive"))
    )
    (net (code "40") (name "Net-(LED4-RA)") (class "Default")
      (node (ref "LED4") (pin "4") (pinfunction "RA_4") (pintype "passive"))
      (node (ref "R27") (pin "1") (pinfunction "1_1") (pintype "passive"))
    )
    (net (code "41") (name "Net-(LED5-BA)") (class "Default")
      (node (ref "LED5") (pin "5") (pinfunction "GA_5") (pintype "passive"))
      (node (ref "LED5") (pin "6") (pinfunction "BA_6") (pintype "passive"))
      (node (ref "Q8") (pin "E") (pinfunction "E_E") (pintype "passive"))
      (node (ref "R28") (pin "2") (pinfunction "2_2") (pintype "passive"))
    )
    (net (code "42") (name "Net-(LED5-RA)") (class "Default")
      (node (ref "LED5") (pin "4") (pinfunction "RA_4") (pintype "passive"))
      (node (ref "R28") (pin "1") (pinfunction "1_1") (pintype "passive"))
    )
    (net (code "43") (name "Net-(LED6-PadA)") (class "Default")
      (node (ref "LED6") (pin "A") (pinfunction "A_A") (pintype "passive"))
      (node (ref "R33") (pin "1") (pinfunction "1_1") (pintype "passive"))
    )
    (net (code "44") (name "Net-(Q1-OE)") (class "Default")
      (node (ref "Q1") (pin "1") (pinfunction "OE_1") (pintype "input"))
      (node (ref "R1") (pin "2") (pinfunction "2_2") (pintype "passive"))
    )
    (net (code "45") (name "Net-(Q2-PadB)") (class "Default")
      (node (ref "Q2") (pin "B") (pinfunction "B_B") (pintype "passive"))
      (node (ref "R11") (pin "1") (pinfunction "1_1") (pintype "passive"))
      (node (ref "R14") (pin "2") (pinfunction "2_2") (pintype "passive"))
    )
    (net (code "46") (name "Net-(Q3-PadB)") (class "Default")
      (node (ref "Q3") (pin "B") (pinfunction "B_B") (pintype "passive"))
      (node (ref "R12") (pin "1") (pinfunction "1_1") (pintype "passive"))
      (node (ref "R15") (pin "2") (pinfunction "2_2") (pintype "passive"))
    )
    (net (code "47") (name "Net-(Q4-PadB)") (class "Default")
      (node (ref "Q4") (pin "B") (pinfunction "B_B") (pintype "passive"))
      (node (ref "R13") (pin "1") (pinfunction "1_1") (pintype "passive"))
      (node (ref "R16") (pin "2") (pinfunction "2_2") (pintype "passive"))
    )
    (net (code "48") (name "Net-(Q5-PadB)") (class "Default")
      (node (ref "Q5") (pin "B") (pinfunction "B_B") (pintype "passive"))
      (node (ref "R19") (pin "2") (pinfunction "2_2") (pintype "passive"))
    )
    (net (code "49") (name "Net-(Q6-PadB)") (class "Default")
      (node (ref "Q6") (pin "B") (pinfunction "B_B") (pintype "passive"))
      (node (ref "R20") (pin "2") (pinfunction "2_2") (pintype "passive"))
    )
    (net (code "50") (name "Net-(Q7-PadB)") (class "Default")
      (node (ref "Q7") (pin "B") (pinfunction "B_B") (pintype "passive"))
      (node (ref "R25") (pin "2") (pinfunction "2_2") (pintype "passive"))
    )
    (net (code "51") (name "Net-(Q8-PadB)") (class "Default")
      (node (ref "Q8") (pin "B") (pinfunction "B_B") (pintype "passive"))
      (node (ref "R26") (pin "2") (pinfunction "2_2") (pintype "passive"))
    )
    (net (code "52") (name "P_BAT1+") (class "Default")
      (node (ref "CON_PROG") (pin "14") (pinfunction "14_14") (pintype "bidirectional"))
      (node (ref "SWITCH_PWR") (pin "3") (pinfunction "S_3") (pintype "passive"))
    )
    (net (code "53") (name "P_BAT2+") (class "Default")
      (node (ref "CON_PROG") (pin "15") (pinfunction "15_15") (pintype "bidirectional"))
      (node (ref "SWITCH_PWR") (pin "6") (pinfunction "S1_6") (pintype "passive"))
    )
    (net (code "54") (name "RESET") (class "Default")
      (node (ref "CON_PROG") (pin "7") (pinfunction "7_7") (pintype "bidirectional"))
      (node (ref "IC1") (pin "29") (pinfunction "PC6(/RESET/PCINT14)_29") (pintype "bidirectional"))
      (node (ref "R2") (pin "2") (pinfunction "2_2") (pintype "passive"))
    )
    (net (code "55") (name "RI2C_EN") (class "Default")
      (node (ref "IC1") (pin "19") (pinfunction "ADC6_19") (pintype "passive"))
    )
    (net (code "56") (name "RSCL") (class "Default")
      (node (ref "CON_PROG") (pin "8") (pinfunction "8_8") (pintype "bidirectional"))
      (node (ref "IC1") (pin "28") (pinfunction "PC5(ADC5/SCL/PCINT13)_28") (pintype "bidirectional"))
      (node (ref "IC2") (pin "1") (pinfunction "SCL_1") (pintype "bidirectional"))
      (node (ref "R34") (pin "1") (pinfunction "1_1") (pintype "passive"))
    )
    (net (code "57") (name "RSDA") (class "Default")
      (node (ref "CON_PROG") (pin "9") (pinfunction "9_9") (pintype "bidirectional"))
      (node (ref "IC1") (pin "27") (pinfunction "PC4(ADC4/SDA/PCINT12)_27") (pintype "bidirectional"))
      (node (ref "IC2") (pin "2") (pinfunction "SDA_2") (pintype "bidirectional"))
      (node (ref "R35") (pin "1") (pinfunction "1_1") (pintype "passive"))
    )
    (net (code "58") (name "RXD") (class "Default")
      (node (ref "IC1") (pin "30") (pinfunction "PD0(RXD/PCINT16)_30") (pintype "bidirectional"))
      (node (ref "IC3") (pin "3") (pinfunction "RXD_3") (pintype "bidirectional"))
    )
    (net (code "59") (name "RXIR") (class "Default")
      (node (ref "IC3") (pin "6") (pinfunction "IR_RXD_6") (pintype "bidirectional"))
      (node (ref "IC4") (pin "3") (pinfunction "RXD_3") (pintype "output"))
    )
    (net (code "60") (name "SCK") (class "Default")
      (node (ref "CON_PROG") (pin "18") (pinfunction "18_18") (pintype "bidirectional"))
      (node (ref "IC1") (pin "17") (pinfunction "PB5(SCK/PCINT5)_17") (pintype "bidirectional"))
    )
    (net (code "61") (name "SCL") (class "Default")
      (node (ref "IC2") (pin "5") (pinfunction "SC0_5") (pintype "bidirectional"))
      (node (ref "IC5") (pin "10") (pinfunction "SCL_10") (pintype "input"))
      (node (ref "IC6") (pin "7") (pinfunction "SCL_7") (pintype "input"))
      (node (ref "IC7") (pin "10") (pinfunction "SCL_10") (pintype "input"))
      (node (ref "IC8") (pin "7") (pinfunction "SCL_7") (pintype "input"))
      (node (ref "R8") (pin "1") (pinfunction "1_1") (pintype "passive"))
    )
    (net (code "62") (name "SDA") (class "Default")
      (node (ref "IC2") (pin "4") (pinfunction "SD0_4") (pintype "bidirectional"))
      (node (ref "IC5") (pin "9") (pinfunction "SDA_9") (pintype "bidirectional"))
      (node (ref "IC6") (pin "6") (pinfunction "SDA_6") (pintype "bidirectional"))
      (node (ref "IC7") (pin "9") (pinfunction "SDA_9") (pintype "bidirectional"))
      (node (ref "IC8") (pin "6") (pinfunction "SDA_6") (pintype "bidirectional"))
      (node (ref "R7") (pin "1") (pinfunction "1_1") (pintype "passive"))
    )
    (net (code "63") (name "SENS_MOTL1") (class "Default")
      (node (ref "IC5") (pin "3") (pinfunction "OUT1_3") (pintype "output"))
      (node (ref "IC6") (pin "1") (pinfunction "V1_1") (pintype "input"))
      (node (ref "R30") (pin "1") (pinfunction "1_1") (pintype "passive"))
    )
    (net (code "64") (name "SENS_MOTL2") (class "Default")
      (node (ref "IC6") (pin "2") (pinfunction "V2_2") (pintype "input"))
      (node (ref "MOT2") (pin "1") (pinfunction "P_1") (pintype "passive"))
      (node (ref "R30") (pin "2") (pinfunction "2_2") (pintype "passive"))
    )
    (net (code "65") (name "SENS_MOTR1") (class "Default")
      (node (ref "IC6") (pin "3") (pinfunction "V3_3") (pintype "input"))
      (node (ref "IC7") (pin "3") (pinfunction "OUT1_3") (pintype "output"))
      (node (ref "R32") (pin "1") (pinfunction "1_1") (pintype "passive"))
    )
    (net (code "66") (name "SENS_MOTR2") (class "Default")
      (node (ref "IC6") (pin "4") (pinfunction "V4_4") (pintype "input"))
      (node (ref "MOT4") (pin "1") (pinfunction "P_1") (pintype "passive"))
      (node (ref "R32") (pin "2") (pinfunction "2_2") (pintype "passive"))
    )
    (net (code "67") (name "SRXD") (class "Default")
      (node (ref "CON_PROG") (pin "11") (pinfunction "11_11") (pintype "bidirectional"))
      (node (ref "IC1") (pin "23") (pinfunction "PC0(ADC0/PCINT8)_23") (pintype "bidirectional"))
    )
    (net (code "68") (name "STXD") (class "Default")
      (node (ref "CON_PROG") (pin "10") (pinfunction "10_10") (pintype "bidirectional"))
      (node (ref "IC1") (pin "24") (pinfunction "PC1(ADC1/PCINT9)_24") (pintype "bidirectional"))
    )
    (net (code "69") (name "TXD") (class "Default")
      (node (ref "IC1") (pin "31") (pinfunction "PD1(TXD/PCINT17)_31") (pintype "bidirectional"))
      (node (ref "IC3") (pin "2") (pinfunction "TXD_2") (pintype "bidirectional"))
    )
    (net (code "70") (name "TXIR") (class "Default")
      (node (ref "IC3") (pin "7") (pinfunction "IR_TXD_7") (pintype "bidirectional"))
      (node (ref "IC4") (pin "2") (pinfunction "TXD_2") (pintype "input"))
    )
    (net (code "71") (name "VCC") (class "Default")
      (node (ref "C1") (pin "1") (pinfunction "1_1") (pintype "passive"))
      (node (ref "C5") (pin "1") (pinfunction "1_1") (pintype "passive"))
      (node (ref "CON_PROG") (pin "1") (pinfunction "1_1") (pintype "bidirectional"))
      (node (ref "D1") (pin "C") (pinfunction "C_C") (pintype "passive"))
      (node (ref "D2") (pin "C") (pinfunction "C_C") (pintype "passive"))
      (node (ref "IC1") (pin "18") (pinfunction "AVCC_18") (pintype "passive"))
      (node (ref "IC1") (pin "4") (pinfunction "VCC_4") (pintype "power_in"))
      (node (ref "IC1") (pin "6") (pinfunction "VCC_6") (pintype "power_in"))
      (node (ref "IC2") (pin "3") (pinfunction "VCC_3") (pintype "bidirectional"))
      (node (ref "IC3") (pin "8") (pinfunction "VCC_8") (pintype "bidirectional"))
      (node (ref "IC4") (pin "5") (pinfunction "VCC_5") (pintype "power_in"))
      (node (ref "IC5") (pin "4") (pinfunction "VCC_4") (pintype "power_in"))
      (node (ref "IC6") (pin "10") (pinfunction "VCC_10") (pintype "power_in"))
      (node (ref "IC7") (pin "4") (pinfunction "VCC_4") (pintype "power_in"))
      (node (ref "IC7") (pin "7") (pinfunction "A0_7") (pintype "input"))
      (node (ref "IC8") (pin "10") (pinfunction "VCC_10") (pintype "power_in"))
      (node (ref "IC8") (pin "8") (pinfunction "ADR0_8") (pintype "input"))
      (node (ref "Q1") (pin "4") (pinfunction "VCC_4") (pintype "power_in"))
      (node (ref "Q5") (pin "C") (pinfunction "C_C") (pintype "passive"))
      (node (ref "Q6") (pin "C") (pinfunction "C_C") (pintype "passive"))
      (node (ref "Q7") (pin "C") (pinfunction "C_C") (pintype "passive"))
      (node (ref "Q8") (pin "C") (pinfunction "C_C") (pintype "passive"))
      (node (ref "R1") (pin "1") (pinfunction "1_1") (pintype "passive"))
      (node (ref "R10") (pin "1") (pinfunction "1_1") (pintype "passive"))
      (node (ref "R2") (pin "1") (pinfunction "1_1") (pintype "passive"))
      (node (ref "R33") (pin "2") (pinfunction "2_2") (pintype "passive"))
      (node (ref "R34") (pin "2") (pinfunction "2_2") (pintype "passive"))
      (node (ref "R35") (pin "2") (pinfunction "2_2") (pintype "passive"))
      (node (ref "R4") (pin "1") (pinfunction "1_1") (pintype "passive"))
      (node (ref "R5") (pin "1") (pinfunction "1_1") (pintype "passive"))
      (node (ref "R7") (pin "2") (pinfunction "2_2") (pintype "passive"))
      (node (ref "R8") (pin "2") (pinfunction "2_2") (pintype "passive"))
    )
    (net (code "72") (name "unconnected-(CON_PROG-Pad6)") (class "Default")
      (node (ref "CON_PROG") (pin "6") (pinfunction "6_6") (pintype "bidirectional"))
    )
    (net (code "73") (name "unconnected-(IC2-SC1-Pad8)") (class "Default")
      (node (ref "IC2") (pin "8") (pinfunction "SC1_8") (pintype "bidirectional"))
    )
    (net (code "74") (name "unconnected-(IC2-SD1-Pad7)") (class "Default")
      (node (ref "IC2") (pin "7") (pinfunction "SD1_7") (pintype "bidirectional"))
    )
    (net (code "75") (name "unconnected-(IC5-FAULTN-Pad6)") (class "Default")
      (node (ref "IC5") (pin "6") (pinfunction "FAULTN_6") (pintype "output"))
    )
    (net (code "76") (name "unconnected-(IC7-FAULTN-Pad6)") (class "Default")
      (node (ref "IC7") (pin "6") (pinfunction "FAULTN_6") (pintype "output"))
    )
  )
)
